# Protoboard_MX4-7-9.net
KiCad netlist of a schematic drawn in EAGLE
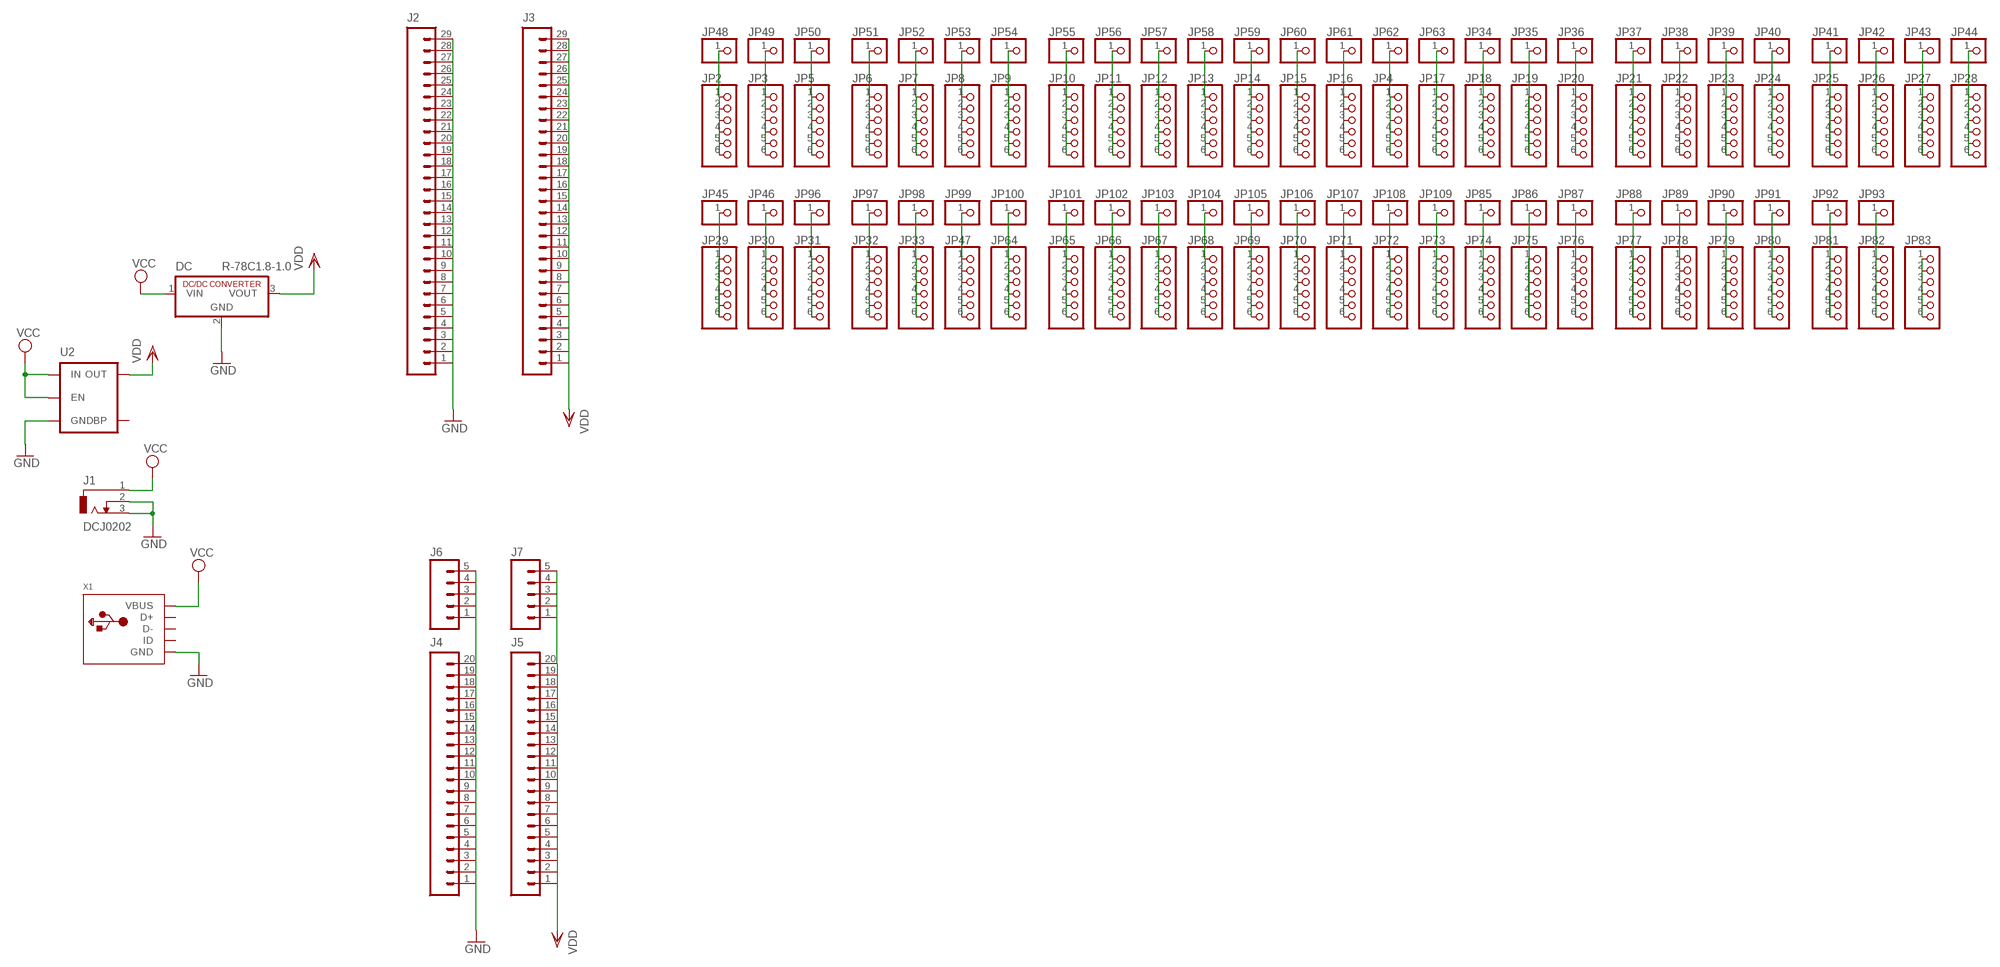
[diagram p0: schematic, sheet 1]

(export (version "E")
  (design (tool "Eeschema 10.0.6"))
  (components
    (comp (ref "DC")
      (value "R-78C1.8-1.0")
      (footprint "eagle-import:SIP3")
      (libsource (lib "eagle-import") (part "R-78C-1.01.8"))
    )
    (comp (ref "J1")
      (value "DCJ0202")
      (footprint "eagle-import:DCJ0202")
      (libsource (lib "eagle-import") (part "DCJ0202"))
    )
    (comp (ref "J2")
      (value "M29NO_SILK")
      (footprint "eagle-import:1X29_NO_SILK")
      (libsource (lib "eagle-import") (part "M29NO_SILK"))
    )
    (comp (ref "J3")
      (value "M29NO_SILK")
      (footprint "eagle-import:1X29_NO_SILK")
      (libsource (lib "eagle-import") (part "M29NO_SILK"))
    )
    (comp (ref "J4")
      (value "M20NO_SILK_KIT")
      (footprint "eagle-import:1X20_NO_SILK_KIT")
      (libsource (lib "eagle-import") (part "M20NO_SILK_KIT"))
    )
    (comp (ref "J5")
      (value "M20NO_SILK_KIT")
      (footprint "eagle-import:1X20_NO_SILK_KIT")
      (libsource (lib "eagle-import") (part "M20NO_SILK_KIT"))
    )
    (comp (ref "J6")
      (value "M05NO_SILK")
      (footprint "eagle-import:1X05_NO_SILK")
      (libsource (lib "eagle-import") (part "M05NO_SILK"))
    )
    (comp (ref "J7")
      (value "M05NO_SILK")
      (footprint "eagle-import:1X05_NO_SILK")
      (libsource (lib "eagle-import") (part "M05NO_SILK"))
    )
    (comp (ref "JP2")
      (value "PINHD-1X6CB")
      (footprint "eagle-import:1X06-CLEANBIG")
      (libsource (lib "eagle-import") (part "PINHD-1X6CB"))
    )
    (comp (ref "JP3")
      (value "PINHD-1X6CB")
      (footprint "eagle-import:1X06-CLEANBIG")
      (libsource (lib "eagle-import") (part "PINHD-1X6CB"))
    )
    (comp (ref "JP4")
      (value "PINHD-1X6CB")
      (footprint "eagle-import:1X06-CLEANBIG")
      (libsource (lib "eagle-import") (part "PINHD-1X6CB"))
    )
    (comp (ref "JP5")
      (value "PINHD-1X6CB")
      (footprint "eagle-import:1X06-CLEANBIG")
      (libsource (lib "eagle-import") (part "PINHD-1X6CB"))
    )
    (comp (ref "JP6")
      (value "PINHD-1X6CB")
      (footprint "eagle-import:1X06-CLEANBIG")
      (libsource (lib "eagle-import") (part "PINHD-1X6CB"))
    )
    (comp (ref "JP7")
      (value "PINHD-1X6CB")
      (footprint "eagle-import:1X06-CLEANBIG")
      (libsource (lib "eagle-import") (part "PINHD-1X6CB"))
    )
    (comp (ref "JP8")
      (value "PINHD-1X6CB")
      (footprint "eagle-import:1X06-CLEANBIG")
      (libsource (lib "eagle-import") (part "PINHD-1X6CB"))
    )
    (comp (ref "JP9")
      (value "PINHD-1X6CB")
      (footprint "eagle-import:1X06-CLEANBIG")
      (libsource (lib "eagle-import") (part "PINHD-1X6CB"))
    )
    (comp (ref "JP10")
      (value "PINHD-1X6CB")
      (footprint "eagle-import:1X06-CLEANBIG")
      (libsource (lib "eagle-import") (part "PINHD-1X6CB"))
    )
    (comp (ref "JP11")
      (value "PINHD-1X6CB")
      (footprint "eagle-import:1X06-CLEANBIG")
      (libsource (lib "eagle-import") (part "PINHD-1X6CB"))
    )
    (comp (ref "JP12")
      (value "PINHD-1X6CB")
      (footprint "eagle-import:1X06-CLEANBIG")
      (libsource (lib "eagle-import") (part "PINHD-1X6CB"))
    )
    (comp (ref "JP13")
      (value "PINHD-1X6CB")
      (footprint "eagle-import:1X06-CLEANBIG")
      (libsource (lib "eagle-import") (part "PINHD-1X6CB"))
    )
    (comp (ref "JP14")
      (value "PINHD-1X6CB")
      (footprint "eagle-import:1X06-CLEANBIG")
      (libsource (lib "eagle-import") (part "PINHD-1X6CB"))
    )
    (comp (ref "JP15")
      (value "PINHD-1X6CB")
      (footprint "eagle-import:1X06-CLEANBIG")
      (libsource (lib "eagle-import") (part "PINHD-1X6CB"))
    )
    (comp (ref "JP16")
      (value "PINHD-1X6CB")
      (footprint "eagle-import:1X06-CLEANBIG")
      (libsource (lib "eagle-import") (part "PINHD-1X6CB"))
    )
    (comp (ref "JP17")
      (value "PINHD-1X6CB")
      (footprint "eagle-import:1X06-CLEANBIG")
      (libsource (lib "eagle-import") (part "PINHD-1X6CB"))
    )
    (comp (ref "JP18")
      (value "PINHD-1X6CB")
      (footprint "eagle-import:1X06-CLEANBIG")
      (libsource (lib "eagle-import") (part "PINHD-1X6CB"))
    )
    (comp (ref "JP19")
      (value "PINHD-1X6CB")
      (footprint "eagle-import:1X06-CLEANBIG")
      (libsource (lib "eagle-import") (part "PINHD-1X6CB"))
    )
    (comp (ref "JP20")
      (value "PINHD-1X6CB")
      (footprint "eagle-import:1X06-CLEANBIG")
      (libsource (lib "eagle-import") (part "PINHD-1X6CB"))
    )
    (comp (ref "JP21")
      (value "PINHD-1X6CB")
      (footprint "eagle-import:1X06-CLEANBIG")
      (libsource (lib "eagle-import") (part "PINHD-1X6CB"))
    )
    (comp (ref "JP22")
      (value "PINHD-1X6CB")
      (footprint "eagle-import:1X06-CLEANBIG")
      (libsource (lib "eagle-import") (part "PINHD-1X6CB"))
    )
    (comp (ref "JP23")
      (value "PINHD-1X6CB")
      (footprint "eagle-import:1X06-CLEANBIG")
      (libsource (lib "eagle-import") (part "PINHD-1X6CB"))
    )
    (comp (ref "JP24")
      (value "PINHD-1X6CB")
      (footprint "eagle-import:1X06-CLEANBIG")
      (libsource (lib "eagle-import") (part "PINHD-1X6CB"))
    )
    (comp (ref "JP25")
      (value "PINHD-1X6CB")
      (footprint "eagle-import:1X06-CLEANBIG")
      (libsource (lib "eagle-import") (part "PINHD-1X6CB"))
    )
    (comp (ref "JP26")
      (value "PINHD-1X6CB")
      (footprint "eagle-import:1X06-CLEANBIG")
      (libsource (lib "eagle-import") (part "PINHD-1X6CB"))
    )
    (comp (ref "JP27")
      (value "PINHD-1X6CB")
      (footprint "eagle-import:1X06-CLEANBIG")
      (libsource (lib "eagle-import") (part "PINHD-1X6CB"))
    )
    (comp (ref "JP28")
      (value "PINHD-1X6CB")
      (footprint "eagle-import:1X06-CLEANBIG")
      (libsource (lib "eagle-import") (part "PINHD-1X6CB"))
    )
    (comp (ref "JP29")
      (value "PINHD-1X6CB")
      (footprint "eagle-import:1X06-CLEANBIG")
      (libsource (lib "eagle-import") (part "PINHD-1X6CB"))
    )
    (comp (ref "JP30")
      (value "PINHD-1X6CB")
      (footprint "eagle-import:1X06-CLEANBIG")
      (libsource (lib "eagle-import") (part "PINHD-1X6CB"))
    )
    (comp (ref "JP31")
      (value "PINHD-1X6CB")
      (footprint "eagle-import:1X06-CLEANBIG")
      (libsource (lib "eagle-import") (part "PINHD-1X6CB"))
    )
    (comp (ref "JP32")
      (value "PINHD-1X6CB")
      (footprint "eagle-import:1X06-CLEANBIG")
      (libsource (lib "eagle-import") (part "PINHD-1X6CB"))
    )
    (comp (ref "JP33")
      (value "PINHD-1X6CB")
      (footprint "eagle-import:1X06-CLEANBIG")
      (libsource (lib "eagle-import") (part "PINHD-1X6CB"))
    )
    (comp (ref "JP34")
      (value "PINHD-1X1CB")
      (footprint "eagle-import:1X01-CLEANBIG")
      (libsource (lib "eagle-import") (part "PINHD-1X1CB"))
    )
    (comp (ref "JP35")
      (value "PINHD-1X1CB")
      (footprint "eagle-import:1X01-CLEANBIG")
      (libsource (lib "eagle-import") (part "PINHD-1X1CB"))
    )
    (comp (ref "JP36")
      (value "PINHD-1X1CB")
      (footprint "eagle-import:1X01-CLEANBIG")
      (libsource (lib "eagle-import") (part "PINHD-1X1CB"))
    )
    (comp (ref "JP37")
      (value "PINHD-1X1CB")
      (footprint "eagle-import:1X01-CLEANBIG")
      (libsource (lib "eagle-import") (part "PINHD-1X1CB"))
    )
    (comp (ref "JP38")
      (value "PINHD-1X1CB")
      (footprint "eagle-import:1X01-CLEANBIG")
      (libsource (lib "eagle-import") (part "PINHD-1X1CB"))
    )
    (comp (ref "JP39")
      (value "PINHD-1X1CB")
      (footprint "eagle-import:1X01-CLEANBIG")
      (libsource (lib "eagle-import") (part "PINHD-1X1CB"))
    )
    (comp (ref "JP40")
      (value "PINHD-1X1CB")
      (footprint "eagle-import:1X01-CLEANBIG")
      (libsource (lib "eagle-import") (part "PINHD-1X1CB"))
    )
    (comp (ref "JP41")
      (value "PINHD-1X1CB")
      (footprint "eagle-import:1X01-CLEANBIG")
      (libsource (lib "eagle-import") (part "PINHD-1X1CB"))
    )
    (comp (ref "JP42")
      (value "PINHD-1X1CB")
      (footprint "eagle-import:1X01-CLEANBIG")
      (libsource (lib "eagle-import") (part "PINHD-1X1CB"))
    )
    (comp (ref "JP43")
      (value "PINHD-1X1CB")
      (footprint "eagle-import:1X01-CLEANBIG")
      (libsource (lib "eagle-import") (part "PINHD-1X1CB"))
    )
    (comp (ref "JP44")
      (value "PINHD-1X1CB")
      (footprint "eagle-import:1X01-CLEANBIG")
      (libsource (lib "eagle-import") (part "PINHD-1X1CB"))
    )
    (comp (ref "JP45")
      (value "PINHD-1X1CB")
      (footprint "eagle-import:1X01-CLEANBIG")
      (libsource (lib "eagle-import") (part "PINHD-1X1CB"))
    )
    (comp (ref "JP46")
      (value "PINHD-1X1CB")
      (footprint "eagle-import:1X01-CLEANBIG")
      (libsource (lib "eagle-import") (part "PINHD-1X1CB"))
    )
    (comp (ref "JP47")
      (value "PINHD-1X6CB")
      (footprint "eagle-import:1X06-CLEANBIG")
      (libsource (lib "eagle-import") (part "PINHD-1X6CB"))
    )
    (comp (ref "JP48")
      (value "PINHD-1X1CB")
      (footprint "eagle-import:1X01-CLEANBIG")
      (libsource (lib "eagle-import") (part "PINHD-1X1CB"))
    )
    (comp (ref "JP49")
      (value "PINHD-1X1CB")
      (footprint "eagle-import:1X01-CLEANBIG")
      (libsource (lib "eagle-import") (part "PINHD-1X1CB"))
    )
    (comp (ref "JP50")
      (value "PINHD-1X1CB")
      (footprint "eagle-import:1X01-CLEANBIG")
      (libsource (lib "eagle-import") (part "PINHD-1X1CB"))
    )
    (comp (ref "JP51")
      (value "PINHD-1X1CB")
      (footprint "eagle-import:1X01-CLEANBIG")
      (libsource (lib "eagle-import") (part "PINHD-1X1CB"))
    )
    (comp (ref "JP52")
      (value "PINHD-1X1CB")
      (footprint "eagle-import:1X01-CLEANBIG")
      (libsource (lib "eagle-import") (part "PINHD-1X1CB"))
    )
    (comp (ref "JP53")
      (value "PINHD-1X1CB")
      (footprint "eagle-import:1X01-CLEANBIG")
      (libsource (lib "eagle-import") (part "PINHD-1X1CB"))
    )
    (comp (ref "JP54")
      (value "PINHD-1X1CB")
      (footprint "eagle-import:1X01-CLEANBIG")
      (libsource (lib "eagle-import") (part "PINHD-1X1CB"))
    )
    (comp (ref "JP55")
      (value "PINHD-1X1CB")
      (footprint "eagle-import:1X01-CLEANBIG")
      (libsource (lib "eagle-import") (part "PINHD-1X1CB"))
    )
    (comp (ref "JP56")
      (value "PINHD-1X1CB")
      (footprint "eagle-import:1X01-CLEANBIG")
      (libsource (lib "eagle-import") (part "PINHD-1X1CB"))
    )
    (comp (ref "JP57")
      (value "PINHD-1X1CB")
      (footprint "eagle-import:1X01-CLEANBIG")
      (libsource (lib "eagle-import") (part "PINHD-1X1CB"))
    )
    (comp (ref "JP58")
      (value "PINHD-1X1CB")
      (footprint "eagle-import:1X01-CLEANBIG")
      (libsource (lib "eagle-import") (part "PINHD-1X1CB"))
    )
    (comp (ref "JP59")
      (value "PINHD-1X1CB")
      (footprint "eagle-import:1X01-CLEANBIG")
      (libsource (lib "eagle-import") (part "PINHD-1X1CB"))
    )
    (comp (ref "JP60")
      (value "PINHD-1X1CB")
      (footprint "eagle-import:1X01-CLEANBIG")
      (libsource (lib "eagle-import") (part "PINHD-1X1CB"))
    )
    (comp (ref "JP61")
      (value "PINHD-1X1CB")
      (footprint "eagle-import:1X01-CLEANBIG")
      (libsource (lib "eagle-import") (part "PINHD-1X1CB"))
    )
    (comp (ref "JP62")
      (value "PINHD-1X1CB")
      (footprint "eagle-import:1X01-CLEANBIG")
      (libsource (lib "eagle-import") (part "PINHD-1X1CB"))
    )
    (comp (ref "JP63")
      (value "PINHD-1X1CB")
      (footprint "eagle-import:1X01-CLEANBIG")
      (libsource (lib "eagle-import") (part "PINHD-1X1CB"))
    )
    (comp (ref "JP64")
      (value "PINHD-1X6CB")
      (footprint "eagle-import:1X06-CLEANBIG")
      (libsource (lib "eagle-import") (part "PINHD-1X6CB"))
    )
    (comp (ref "JP65")
      (value "PINHD-1X6CB")
      (footprint "eagle-import:1X06-CLEANBIG")
      (libsource (lib "eagle-import") (part "PINHD-1X6CB"))
    )
    (comp (ref "JP66")
      (value "PINHD-1X6CB")
      (footprint "eagle-import:1X06-CLEANBIG")
      (libsource (lib "eagle-import") (part "PINHD-1X6CB"))
    )
    (comp (ref "JP67")
      (value "PINHD-1X6CB")
      (footprint "eagle-import:1X06-CLEANBIG")
      (libsource (lib "eagle-import") (part "PINHD-1X6CB"))
    )
    (comp (ref "JP68")
      (value "PINHD-1X6CB")
      (footprint "eagle-import:1X06-CLEANBIG")
      (libsource (lib "eagle-import") (part "PINHD-1X6CB"))
    )
    (comp (ref "JP69")
      (value "PINHD-1X6CB")
      (footprint "eagle-import:1X06-CLEANBIG")
      (libsource (lib "eagle-import") (part "PINHD-1X6CB"))
    )
    (comp (ref "JP70")
      (value "PINHD-1X6CB")
      (footprint "eagle-import:1X06-CLEANBIG")
      (libsource (lib "eagle-import") (part "PINHD-1X6CB"))
    )
    (comp (ref "JP71")
      (value "PINHD-1X6CB")
      (footprint "eagle-import:1X06-CLEANBIG")
      (libsource (lib "eagle-import") (part "PINHD-1X6CB"))
    )
    (comp (ref "JP72")
      (value "PINHD-1X6CB")
      (footprint "eagle-import:1X06-CLEANBIG")
      (libsource (lib "eagle-import") (part "PINHD-1X6CB"))
    )
    (comp (ref "JP73")
      (value "PINHD-1X6CB")
      (footprint "eagle-import:1X06-CLEANBIG")
      (libsource (lib "eagle-import") (part "PINHD-1X6CB"))
    )
    (comp (ref "JP74")
      (value "PINHD-1X6CB")
      (footprint "eagle-import:1X06-CLEANBIG")
      (libsource (lib "eagle-import") (part "PINHD-1X6CB"))
    )
    (comp (ref "JP75")
      (value "PINHD-1X6CB")
      (footprint "eagle-import:1X06-CLEANBIG")
      (libsource (lib "eagle-import") (part "PINHD-1X6CB"))
    )
    (comp (ref "JP76")
      (value "PINHD-1X6CB")
      (footprint "eagle-import:1X06-CLEANBIG")
      (libsource (lib "eagle-import") (part "PINHD-1X6CB"))
    )
    (comp (ref "JP77")
      (value "PINHD-1X6CB")
      (footprint "eagle-import:1X06-CLEANBIG")
      (libsource (lib "eagle-import") (part "PINHD-1X6CB"))
    )
    (comp (ref "JP78")
      (value "PINHD-1X6CB")
      (footprint "eagle-import:1X06-CLEANBIG")
      (libsource (lib "eagle-import") (part "PINHD-1X6CB"))
    )
    (comp (ref "JP79")
      (value "PINHD-1X6CB")
      (footprint "eagle-import:1X06-CLEANBIG")
      (libsource (lib "eagle-import") (part "PINHD-1X6CB"))
    )
    (comp (ref "JP80")
      (value "PINHD-1X6CB")
      (footprint "eagle-import:1X06-CLEANBIG")
      (libsource (lib "eagle-import") (part "PINHD-1X6CB"))
    )
    (comp (ref "JP81")
      (value "PINHD-1X6CB")
      (footprint "eagle-import:1X06-CLEANBIG")
      (libsource (lib "eagle-import") (part "PINHD-1X6CB"))
    )
    (comp (ref "JP82")
      (value "PINHD-1X6CB")
      (footprint "eagle-import:1X06-CLEANBIG")
      (libsource (lib "eagle-import") (part "PINHD-1X6CB"))
    )
    (comp (ref "JP83")
      (value "PINHD-1X6CB")
      (footprint "eagle-import:1X06-CLEANBIG")
      (libsource (lib "eagle-import") (part "PINHD-1X6CB"))
    )
    (comp (ref "JP85")
      (value "PINHD-1X1CB")
      (footprint "eagle-import:1X01-CLEANBIG")
      (libsource (lib "eagle-import") (part "PINHD-1X1CB"))
    )
    (comp (ref "JP86")
      (value "PINHD-1X1CB")
      (footprint "eagle-import:1X01-CLEANBIG")
      (libsource (lib "eagle-import") (part "PINHD-1X1CB"))
    )
    (comp (ref "JP87")
      (value "PINHD-1X1CB")
      (footprint "eagle-import:1X01-CLEANBIG")
      (libsource (lib "eagle-import") (part "PINHD-1X1CB"))
    )
    (comp (ref "JP88")
      (value "PINHD-1X1CB")
      (footprint "eagle-import:1X01-CLEANBIG")
      (libsource (lib "eagle-import") (part "PINHD-1X1CB"))
    )
    (comp (ref "JP89")
      (value "PINHD-1X1CB")
      (footprint "eagle-import:1X01-CLEANBIG")
      (libsource (lib "eagle-import") (part "PINHD-1X1CB"))
    )
    (comp (ref "JP90")
      (value "PINHD-1X1CB")
      (footprint "eagle-import:1X01-CLEANBIG")
      (libsource (lib "eagle-import") (part "PINHD-1X1CB"))
    )
    (comp (ref "JP91")
      (value "PINHD-1X1CB")
      (footprint "eagle-import:1X01-CLEANBIG")
      (libsource (lib "eagle-import") (part "PINHD-1X1CB"))
    )
    (comp (ref "JP92")
      (value "PINHD-1X1CB")
      (footprint "eagle-import:1X01-CLEANBIG")
      (libsource (lib "eagle-import") (part "PINHD-1X1CB"))
    )
    (comp (ref "JP93")
      (value "PINHD-1X1CB")
      (footprint "eagle-import:1X01-CLEANBIG")
      (libsource (lib "eagle-import") (part "PINHD-1X1CB"))
    )
    (comp (ref "JP96")
      (value "PINHD-1X1CB")
      (footprint "eagle-import:1X01-CLEANBIG")
      (libsource (lib "eagle-import") (part "PINHD-1X1CB"))
    )
    (comp (ref "JP97")
      (value "PINHD-1X1CB")
      (footprint "eagle-import:1X01-CLEANBIG")
      (libsource (lib "eagle-import") (part "PINHD-1X1CB"))
    )
    (comp (ref "JP98")
      (value "PINHD-1X1CB")
      (footprint "eagle-import:1X01-CLEANBIG")
      (libsource (lib "eagle-import") (part "PINHD-1X1CB"))
    )
    (comp (ref "JP99")
      (value "PINHD-1X1CB")
      (footprint "eagle-import:1X01-CLEANBIG")
      (libsource (lib "eagle-import") (part "PINHD-1X1CB"))
    )
    (comp (ref "JP100")
      (value "PINHD-1X1CB")
      (footprint "eagle-import:1X01-CLEANBIG")
      (libsource (lib "eagle-import") (part "PINHD-1X1CB"))
    )
    (comp (ref "JP101")
      (value "PINHD-1X1CB")
      (footprint "eagle-import:1X01-CLEANBIG")
      (libsource (lib "eagle-import") (part "PINHD-1X1CB"))
    )
    (comp (ref "JP102")
      (value "PINHD-1X1CB")
      (footprint "eagle-import:1X01-CLEANBIG")
      (libsource (lib "eagle-import") (part "PINHD-1X1CB"))
    )
    (comp (ref "JP103")
      (value "PINHD-1X1CB")
      (footprint "eagle-import:1X01-CLEANBIG")
      (libsource (lib "eagle-import") (part "PINHD-1X1CB"))
    )
    (comp (ref "JP104")
      (value "PINHD-1X1CB")
      (footprint "eagle-import:1X01-CLEANBIG")
      (libsource (lib "eagle-import") (part "PINHD-1X1CB"))
    )
    (comp (ref "JP105")
      (value "PINHD-1X1CB")
      (footprint "eagle-import:1X01-CLEANBIG")
      (libsource (lib "eagle-import") (part "PINHD-1X1CB"))
    )
    (comp (ref "JP106")
      (value "PINHD-1X1CB")
      (footprint "eagle-import:1X01-CLEANBIG")
      (libsource (lib "eagle-import") (part "PINHD-1X1CB"))
    )
    (comp (ref "JP107")
      (value "PINHD-1X1CB")
      (footprint "eagle-import:1X01-CLEANBIG")
      (libsource (lib "eagle-import") (part "PINHD-1X1CB"))
    )
    (comp (ref "JP108")
      (value "PINHD-1X1CB")
      (footprint "eagle-import:1X01-CLEANBIG")
      (libsource (lib "eagle-import") (part "PINHD-1X1CB"))
    )
    (comp (ref "JP109")
      (value "PINHD-1X1CB")
      (footprint "eagle-import:1X01-CLEANBIG")
      (libsource (lib "eagle-import") (part "PINHD-1X1CB"))
    )
    (comp (ref "U2")
      (value "MIC52053.3V")
      (footprint "eagle-import:SOT23-5")
      (libsource (lib "eagle-import") (part "MIC52053.3V"))
    )
    (comp (ref "X1")
      (value "USBMICRO_20329")
      (footprint "eagle-import:4UCONN_20329")
      (libsource (lib "eagle-import") (part "USBMICRO_20329"))
    )
  )
  (nets
    (net (code "1") (name "GND") (class "Default")
      (node (ref "DC") (pin "2") (pinfunction "GND_2") (pintype "passive"))
      (node (ref "J1") (pin "2") (pinfunction "2_2") (pintype "passive"))
      (node (ref "J1") (pin "3") (pinfunction "3_3") (pintype "passive"))
      (node (ref "J2") (pin "1") (pinfunction "1_1") (pintype "passive"))
      (node (ref "J2") (pin "10") (pinfunction "10_10") (pintype "passive"))
      (node (ref "J2") (pin "11") (pinfunction "11_11") (pintype "passive"))
      (node (ref "J2") (pin "12") (pinfunction "12_12") (pintype "passive"))
      (node (ref "J2") (pin "13") (pinfunction "13_13") (pintype "passive"))
      (node (ref "J2") (pin "14") (pinfunction "14_14") (pintype "passive"))
      (node (ref "J2") (pin "15") (pinfunction "15_15") (pintype "passive"))
      (node (ref "J2") (pin "16") (pinfunction "16_16") (pintype "passive"))
      (node (ref "J2") (pin "17") (pinfunction "17_17") (pintype "passive"))
      (node (ref "J2") (pin "18") (pinfunction "18_18") (pintype "passive"))
      (node (ref "J2") (pin "19") (pinfunction "19_19") (pintype "passive"))
      (node (ref "J2") (pin "2") (pinfunction "2_2") (pintype "passive"))
      (node (ref "J2") (pin "20") (pinfunction "20_20") (pintype "passive"))
      (node (ref "J2") (pin "21") (pinfunction "21_21") (pintype "passive"))
      (node (ref "J2") (pin "22") (pinfunction "22_22") (pintype "passive"))
      (node (ref "J2") (pin "23") (pinfunction "23_23") (pintype "passive"))
      (node (ref "J2") (pin "24") (pinfunction "24_24") (pintype "passive"))
      (node (ref "J2") (pin "25") (pinfunction "25_25") (pintype "passive"))
      (node (ref "J2") (pin "26") (pinfunction "26_26") (pintype "passive"))
      (node (ref "J2") (pin "27") (pinfunction "27_27") (pintype "passive"))
      (node (ref "J2") (pin "28") (pinfunction "28_28") (pintype "passive"))
      (node (ref "J2") (pin "29") (pinfunction "29_29") (pintype "passive"))
      (node (ref "J2") (pin "3") (pinfunction "3_3") (pintype "passive"))
      (node (ref "J2") (pin "4") (pinfunction "4_4") (pintype "passive"))
      (node (ref "J2") (pin "5") (pinfunction "5_5") (pintype "passive"))
      (node (ref "J2") (pin "6") (pinfunction "6_6") (pintype "passive"))
      (node (ref "J2") (pin "7") (pinfunction "7_7") (pintype "passive"))
      (node (ref "J2") (pin "8") (pinfunction "8_8") (pintype "passive"))
      (node (ref "J2") (pin "9") (pinfunction "9_9") (pintype "passive"))
      (node (ref "J4") (pin "1") (pinfunction "1_1") (pintype "passive"))
      (node (ref "J4") (pin "10") (pinfunction "10_10") (pintype "passive"))
      (node (ref "J4") (pin "11") (pinfunction "11_11") (pintype "passive"))
      (node (ref "J4") (pin "12") (pinfunction "12_12") (pintype "passive"))
      (node (ref "J4") (pin "13") (pinfunction "13_13") (pintype "passive"))
      (node (ref "J4") (pin "14") (pinfunction "14_14") (pintype "passive"))
      (node (ref "J4") (pin "15") (pinfunction "15_15") (pintype "passive"))
      (node (ref "J4") (pin "16") (pinfunction "16_16") (pintype "passive"))
      (node (ref "J4") (pin "17") (pinfunction "17_17") (pintype "passive"))
      (node (ref "J4") (pin "18") (pinfunction "18_18") (pintype "passive"))
      (node (ref "J4") (pin "19") (pinfunction "19_19") (pintype "passive"))
      (node (ref "J4") (pin "2") (pinfunction "2_2") (pintype "passive"))
      (node (ref "J4") (pin "20") (pinfunction "20_20") (pintype "passive"))
      (node (ref "J4") (pin "3") (pinfunction "3_3") (pintype "passive"))
      (node (ref "J4") (pin "4") (pinfunction "4_4") (pintype "passive"))
      (node (ref "J4") (pin "5") (pinfunction "5_5") (pintype "passive"))
      (node (ref "J4") (pin "6") (pinfunction "6_6") (pintype "passive"))
      (node (ref "J4") (pin "7") (pinfunction "7_7") (pintype "passive"))
      (node (ref "J4") (pin "8") (pinfunction "8_8") (pintype "passive"))
      (node (ref "J4") (pin "9") (pinfunction "9_9") (pintype "passive"))
      (node (ref "J6") (pin "1") (pinfunction "1_1") (pintype "passive"))
      (node (ref "J6") (pin "2") (pinfunction "2_2") (pintype "passive"))
      (node (ref "J6") (pin "3") (pinfunction "3_3") (pintype "passive"))
      (node (ref "J6") (pin "4") (pinfunction "4_4") (pintype "passive"))
      (node (ref "J6") (pin "5") (pinfunction "5_5") (pintype "passive"))
      (node (ref "U2") (pin "2") (pinfunction "GND_2") (pintype "input"))
      (node (ref "X1") (pin "BASE@1") (pinfunction "GND_BASE@1") (pintype "power_in"))
      (node (ref "X1") (pin "BASE@2") (pinfunction "GND_BASE@2") (pintype "power_in"))
      (node (ref "X1") (pin "GND") (pinfunction "GND_GND") (pintype "power_in"))
      (node (ref "X1") (pin "SPRT@1") (pinfunction "GND_SPRT@1") (pintype "power_in"))
      (node (ref "X1") (pin "SPRT@2") (pinfunction "GND_SPRT@2") (pintype "power_in"))
      (node (ref "X1") (pin "SPRT@3") (pinfunction "GND_SPRT@3") (pintype "power_in"))
      (node (ref "X1") (pin "SPRT@4") (pinfunction "GND_SPRT@4") (pintype "power_in"))
    )
    (net (code "2") (name "Net-(JP2-Pad1)") (class "Default")
      (node (ref "JP2") (pin "1") (pinfunction "1_1") (pintype "passive"))
      (node (ref "JP2") (pin "2") (pinfunction "2_2") (pintype "passive"))
      (node (ref "JP2") (pin "3") (pinfunction "3_3") (pintype "passive"))
      (node (ref "JP2") (pin "4") (pinfunction "4_4") (pintype "passive"))
      (node (ref "JP2") (pin "5") (pinfunction "5_5") (pintype "passive"))
      (node (ref "JP2") (pin "6") (pinfunction "6_6") (pintype "passive"))
      (node (ref "JP48") (pin "1") (pinfunction "1_1") (pintype "passive"))
    )
    (net (code "3") (name "Net-(JP3-Pad1)") (class "Default")
      (node (ref "JP3") (pin "1") (pinfunction "1_1") (pintype "passive"))
      (node (ref "JP3") (pin "2") (pinfunction "2_2") (pintype "passive"))
      (node (ref "JP3") (pin "3") (pinfunction "3_3") (pintype "passive"))
      (node (ref "JP3") (pin "4") (pinfunction "4_4") (pintype "passive"))
      (node (ref "JP3") (pin "5") (pinfunction "5_5") (pintype "passive"))
      (node (ref "JP3") (pin "6") (pinfunction "6_6") (pintype "passive"))
      (node (ref "JP49") (pin "1") (pinfunction "1_1") (pintype "passive"))
    )
    (net (code "4") (name "Net-(JP4-Pad1)") (class "Default")
      (node (ref "JP4") (pin "1") (pinfunction "1_1") (pintype "passive"))
      (node (ref "JP4") (pin "2") (pinfunction "2_2") (pintype "passive"))
      (node (ref "JP4") (pin "3") (pinfunction "3_3") (pintype "passive"))
      (node (ref "JP4") (pin "4") (pinfunction "4_4") (pintype "passive"))
      (node (ref "JP4") (pin "5") (pinfunction "5_5") (pintype "passive"))
      (node (ref "JP4") (pin "6") (pinfunction "6_6") (pintype "passive"))
      (node (ref "JP62") (pin "1") (pinfunction "1_1") (pintype "passive"))
    )
    (net (code "5") (name "Net-(JP5-Pad1)") (class "Default")
      (node (ref "JP5") (pin "1") (pinfunction "1_1") (pintype "passive"))
      (node (ref "JP5") (pin "2") (pinfunction "2_2") (pintype "passive"))
      (node (ref "JP5") (pin "3") (pinfunction "3_3") (pintype "passive"))
      (node (ref "JP5") (pin "4") (pinfunction "4_4") (pintype "passive"))
      (node (ref "JP5") (pin "5") (pinfunction "5_5") (pintype "passive"))
      (node (ref "JP5") (pin "6") (pinfunction "6_6") (pintype "passive"))
      (node (ref "JP50") (pin "1") (pinfunction "1_1") (pintype "passive"))
    )
    (net (code "6") (name "Net-(JP10-Pad1)") (class "Default")
      (node (ref "JP10") (pin "1") (pinfunction "1_1") (pintype "passive"))
      (node (ref "JP10") (pin "2") (pinfunction "2_2") (pintype "passive"))
      (node (ref "JP10") (pin "3") (pinfunction "3_3") (pintype "passive"))
      (node (ref "JP10") (pin "4") (pinfunction "4_4") (pintype "passive"))
      (node (ref "JP10") (pin "5") (pinfunction "5_5") (pintype "passive"))
      (node (ref "JP10") (pin "6") (pinfunction "6_6") (pintype "passive"))
      (node (ref "JP55") (pin "1") (pinfunction "1_1") (pintype "passive"))
    )
    (net (code "7") (name "Net-(JP11-Pad1)") (class "Default")
      (node (ref "JP11") (pin "1") (pinfunction "1_1") (pintype "passive"))
      (node (ref "JP11") (pin "2") (pinfunction "2_2") (pintype "passive"))
      (node (ref "JP11") (pin "3") (pinfunction "3_3") (pintype "passive"))
      (node (ref "JP11") (pin "4") (pinfunction "4_4") (pintype "passive"))
      (node (ref "JP11") (pin "5") (pinfunction "5_5") (pintype "passive"))
      (node (ref "JP11") (pin "6") (pinfunction "6_6") (pintype "passive"))
      (node (ref "JP56") (pin "1") (pinfunction "1_1") (pintype "passive"))
    )
    (net (code "8") (name "Net-(JP12-Pad1)") (class "Default")
      (node (ref "JP12") (pin "1") (pinfunction "1_1") (pintype "passive"))
      (node (ref "JP12") (pin "2") (pinfunction "2_2") (pintype "passive"))
      (node (ref "JP12") (pin "3") (pinfunction "3_3") (pintype "passive"))
      (node (ref "JP12") (pin "4") (pinfunction "4_4") (pintype "passive"))
      (node (ref "JP12") (pin "5") (pinfunction "5_5") (pintype "passive"))
      (node (ref "JP12") (pin "6") (pinfunction "6_6") (pintype "passive"))
      (node (ref "JP57") (pin "1") (pinfunction "1_1") (pintype "passive"))
    )
    (net (code "9") (name "Net-(JP13-Pad1)") (class "Default")
      (node (ref "JP13") (pin "1") (pinfunction "1_1") (pintype "passive"))
      (node (ref "JP13") (pin "2") (pinfunction "2_2") (pintype "passive"))
      (node (ref "JP13") (pin "3") (pinfunction "3_3") (pintype "passive"))
      (node (ref "JP13") (pin "4") (pinfunction "4_4") (pintype "passive"))
      (node (ref "JP13") (pin "5") (pinfunction "5_5") (pintype "passive"))
      (node (ref "JP13") (pin "6") (pinfunction "6_6") (pintype "passive"))
      (node (ref "JP58") (pin "1") (pinfunction "1_1") (pintype "passive"))
    )
    (net (code "10") (name "Net-(JP14-Pad1)") (class "Default")
      (node (ref "JP14") (pin "1") (pinfunction "1_1") (pintype "passive"))
      (node (ref "JP14") (pin "2") (pinfunction "2_2") (pintype "passive"))
      (node (ref "JP14") (pin "3") (pinfunction "3_3") (pintype "passive"))
      (node (ref "JP14") (pin "4") (pinfunction "4_4") (pintype "passive"))
      (node (ref "JP14") (pin "5") (pinfunction "5_5") (pintype "passive"))
      (node (ref "JP14") (pin "6") (pinfunction "6_6") (pintype "passive"))
      (node (ref "JP59") (pin "1") (pinfunction "1_1") (pintype "passive"))
    )
    (net (code "11") (name "Net-(JP15-Pad1)") (class "Default")
      (node (ref "JP15") (pin "1") (pinfunction "1_1") (pintype "passive"))
      (node (ref "JP15") (pin "2") (pinfunction "2_2") (pintype "passive"))
      (node (ref "JP15") (pin "3") (pinfunction "3_3") (pintype "passive"))
      (node (ref "JP15") (pin "4") (pinfunction "4_4") (pintype "passive"))
      (node (ref "JP15") (pin "5") (pinfunction "5_5") (pintype "passive"))
      (node (ref "JP15") (pin "6") (pinfunction "6_6") (pintype "passive"))
      (node (ref "JP60") (pin "1") (pinfunction "1_1") (pintype "passive"))
    )
    (net (code "12") (name "Net-(JP16-Pad1)") (class "Default")
      (node (ref "JP16") (pin "1") (pinfunction "1_1") (pintype "passive"))
      (node (ref "JP16") (pin "2") (pinfunction "2_2") (pintype "passive"))
      (node (ref "JP16") (pin "3") (pinfunction "3_3") (pintype "passive"))
      (node (ref "JP16") (pin "4") (pinfunction "4_4") (pintype "passive"))
      (node (ref "JP16") (pin "5") (pinfunction "5_5") (pintype "passive"))
      (node (ref "JP16") (pin "6") (pinfunction "6_6") (pintype "passive"))
      (node (ref "JP61") (pin "1") (pinfunction "1_1") (pintype "passive"))
    )
    (net (code "13") (name "Net-(JP17-Pad1)") (class "Default")
      (node (ref "JP17") (pin "1") (pinfunction "1_1") (pintype "passive"))
      (node (ref "JP17") (pin "2") (pinfunction "2_2") (pintype "passive"))
      (node (ref "JP17") (pin "3") (pinfunction "3_3") (pintype "passive"))
      (node (ref "JP17") (pin "4") (pinfunction "4_4") (pintype "passive"))
      (node (ref "JP17") (pin "5") (pinfunction "5_5") (pintype "passive"))
      (node (ref "JP17") (pin "6") (pinfunction "6_6") (pintype "passive"))
      (node (ref "JP63") (pin "1") (pinfunction "1_1") (pintype "passive"))
    )
    (net (code "14") (name "Net-(JP18-Pad1)") (class "Default")
      (node (ref "JP18") (pin "1") (pinfunction "1_1") (pintype "passive"))
      (node (ref "JP18") (pin "2") (pinfunction "2_2") (pintype "passive"))
      (node (ref "JP18") (pin "3") (pinfunction "3_3") (pintype "passive"))
      (node (ref "JP18") (pin "4") (pinfunction "4_4") (pintype "passive"))
      (node (ref "JP18") (pin "5") (pinfunction "5_5") (pintype "passive"))
      (node (ref "JP18") (pin "6") (pinfunction "6_6") (pintype "passive"))
      (node (ref "JP34") (pin "1") (pinfunction "1_1") (pintype "passive"))
    )
    (net (code "15") (name "Net-(JP19-Pad1)") (class "Default")
      (node (ref "JP19") (pin "1") (pinfunction "1_1") (pintype "passive"))
      (node (ref "JP19") (pin "2") (pinfunction "2_2") (pintype "passive"))
      (node (ref "JP19") (pin "3") (pinfunction "3_3") (pintype "passive"))
      (node (ref "JP19") (pin "4") (pinfunction "4_4") (pintype "passive"))
      (node (ref "JP19") (pin "5") (pinfunction "5_5") (pintype "passive"))
      (node (ref "JP19") (pin "6") (pinfunction "6_6") (pintype "passive"))
      (node (ref "JP35") (pin "1") (pinfunction "1_1") (pintype "passive"))
    )
    (net (code "16") (name "Net-(JP20-Pad1)") (class "Default")
      (node (ref "JP20") (pin "1") (pinfunction "1_1") (pintype "passive"))
      (node (ref "JP20") (pin "2") (pinfunction "2_2") (pintype "passive"))
      (node (ref "JP20") (pin "3") (pinfunction "3_3") (pintype "passive"))
      (node (ref "JP20") (pin "4") (pinfunction "4_4") (pintype "passive"))
      (node (ref "JP20") (pin "5") (pinfunction "5_5") (pintype "passive"))
      (node (ref "JP20") (pin "6") (pinfunction "6_6") (pintype "passive"))
      (node (ref "JP36") (pin "1") (pinfunction "1_1") (pintype "passive"))
    )
    (net (code "17") (name "Net-(JP21-Pad1)") (class "Default")
      (node (ref "JP21") (pin "1") (pinfunction "1_1") (pintype "passive"))
      (node (ref "JP21") (pin "2") (pinfunction "2_2") (pintype "passive"))
      (node (ref "JP21") (pin "3") (pinfunction "3_3") (pintype "passive"))
      (node (ref "JP21") (pin "4") (pinfunction "4_4") (pintype "passive"))
      (node (ref "JP21") (pin "5") (pinfunction "5_5") (pintype "passive"))
      (node (ref "JP21") (pin "6") (pinfunction "6_6") (pintype "passive"))
      (node (ref "JP37") (pin "1") (pinfunction "1_1") (pintype "passive"))
    )
    (net (code "18") (name "Net-(JP22-Pad1)") (class "Default")
      (node (ref "JP22") (pin "1") (pinfunction "1_1") (pintype "passive"))
      (node (ref "JP22") (pin "2") (pinfunction "2_2") (pintype "passive"))
      (node (ref "JP22") (pin "3") (pinfunction "3_3") (pintype "passive"))
      (node (ref "JP22") (pin "4") (pinfunction "4_4") (pintype "passive"))
      (node (ref "JP22") (pin "5") (pinfunction "5_5") (pintype "passive"))
      (node (ref "JP22") (pin "6") (pinfunction "6_6") (pintype "passive"))
      (node (ref "JP38") (pin "1") (pinfunction "1_1") (pintype "passive"))
    )
    (net (code "19") (name "Net-(JP23-Pad1)") (class "Default")
      (node (ref "JP23") (pin "1") (pinfunction "1_1") (pintype "passive"))
      (node (ref "JP23") (pin "2") (pinfunction "2_2") (pintype "passive"))
      (node (ref "JP23") (pin "3") (pinfunction "3_3") (pintype "passive"))
      (node (ref "JP23") (pin "4") (pinfunction "4_4") (pintype "passive"))
      (node (ref "JP23") (pin "5") (pinfunction "5_5") (pintype "passive"))
      (node (ref "JP23") (pin "6") (pinfunction "6_6") (pintype "passive"))
      (node (ref "JP39") (pin "1") (pinfunction "1_1") (pintype "passive"))
    )
    (net (code "20") (name "Net-(JP24-Pad1)") (class "Default")
      (node (ref "JP24") (pin "1") (pinfunction "1_1") (pintype "passive"))
      (node (ref "JP24") (pin "2") (pinfunction "2_2") (pintype "passive"))
      (node (ref "JP24") (pin "3") (pinfunction "3_3") (pintype "passive"))
      (node (ref "JP24") (pin "4") (pinfunction "4_4") (pintype "passive"))
      (node (ref "JP24") (pin "5") (pinfunction "5_5") (pintype "passive"))
      (node (ref "JP24") (pin "6") (pinfunction "6_6") (pintype "passive"))
      (node (ref "JP40") (pin "1") (pinfunction "1_1") (pintype "passive"))
    )
    (net (code "21") (name "Net-(JP25-Pad1)") (class "Default")
      (node (ref "JP25") (pin "1") (pinfunction "1_1") (pintype "passive"))
      (node (ref "JP25") (pin "2") (pinfunction "2_2") (pintype "passive"))
      (node (ref "JP25") (pin "3") (pinfunction "3_3") (pintype "passive"))
      (node (ref "JP25") (pin "4") (pinfunction "4_4") (pintype "passive"))
      (node (ref "JP25") (pin "5") (pinfunction "5_5") (pintype "passive"))
      (node (ref "JP25") (pin "6") (pinfunction "6_6") (pintype "passive"))
      (node (ref "JP41") (pin "1") (pinfunction "1_1") (pintype "passive"))
    )
    (net (code "22") (name "Net-(JP26-Pad1)") (class "Default")
      (node (ref "JP26") (pin "1") (pinfunction "1_1") (pintype "passive"))
      (node (ref "JP26") (pin "2") (pinfunction "2_2") (pintype "passive"))
      (node (ref "JP26") (pin "3") (pinfunction "3_3") (pintype "passive"))
      (node (ref "JP26") (pin "4") (pinfunction "4_4") (pintype "passive"))
      (node (ref "JP26") (pin "5") (pinfunction "5_5") (pintype "passive"))
      (node (ref "JP26") (pin "6") (pinfunction "6_6") (pintype "passive"))
      (node (ref "JP42") (pin "1") (pinfunction "1_1") (pintype "passive"))
    )
    (net (code "23") (name "Net-(JP27-Pad1)") (class "Default")
      (node (ref "JP27") (pin "1") (pinfunction "1_1") (pintype "passive"))
      (node (ref "JP27") (pin "2") (pinfunction "2_2") (pintype "passive"))
      (node (ref "JP27") (pin "3") (pinfunction "3_3") (pintype "passive"))
      (node (ref "JP27") (pin "4") (pinfunction "4_4") (pintype "passive"))
      (node (ref "JP27") (pin "5") (pinfunction "5_5") (pintype "passive"))
      (node (ref "JP27") (pin "6") (pinfunction "6_6") (pintype "passive"))
      (node (ref "JP43") (pin "1") (pinfunction "1_1") (pintype "passive"))
    )
    (net (code "24") (name "Net-(JP28-Pad1)") (class "Default")
      (node (ref "JP28") (pin "1") (pinfunction "1_1") (pintype "passive"))
      (node (ref "JP28") (pin "2") (pinfunction "2_2") (pintype "passive"))
      (node (ref "JP28") (pin "3") (pinfunction "3_3") (pintype "passive"))
      (node (ref "JP28") (pin "4") (pinfunction "4_4") (pintype "passive"))
      (node (ref "JP28") (pin "5") (pinfunction "5_5") (pintype "passive"))
      (node (ref "JP28") (pin "6") (pinfunction "6_6") (pintype "passive"))
      (node (ref "JP44") (pin "1") (pinfunction "1_1") (pintype "passive"))
    )
    (net (code "25") (name "Net-(JP29-Pad1)") (class "Default")
      (node (ref "JP29") (pin "1") (pinfunction "1_1") (pintype "passive"))
      (node (ref "JP29") (pin "2") (pinfunction "2_2") (pintype "passive"))
      (node (ref "JP29") (pin "3") (pinfunction "3_3") (pintype "passive"))
      (node (ref "JP29") (pin "4") (pinfunction "4_4") (pintype "passive"))
      (node (ref "JP29") (pin "5") (pinfunction "5_5") (pintype "passive"))
      (node (ref "JP29") (pin "6") (pinfunction "6_6") (pintype "passive"))
      (node (ref "JP45") (pin "1") (pinfunction "1_1") (pintype "passive"))
    )
    (net (code "26") (name "Net-(JP30-Pad1)") (class "Default")
      (node (ref "JP30") (pin "1") (pinfunction "1_1") (pintype "passive"))
      (node (ref "JP30") (pin "2") (pinfunction "2_2") (pintype "passive"))
      (node (ref "JP30") (pin "3") (pinfunction "3_3") (pintype "passive"))
      (node (ref "JP30") (pin "4") (pinfunction "4_4") (pintype "passive"))
      (node (ref "JP30") (pin "5") (pinfunction "5_5") (pintype "passive"))
      (node (ref "JP30") (pin "6") (pinfunction "6_6") (pintype "passive"))
      (node (ref "JP46") (pin "1") (pinfunction "1_1") (pintype "passive"))
    )
    (net (code "27") (name "Net-(JP31-Pad1)") (class "Default")
      (node (ref "JP31") (pin "1") (pinfunction "1_1") (pintype "passive"))
      (node (ref "JP31") (pin "2") (pinfunction "2_2") (pintype "passive"))
      (node (ref "JP31") (pin "3") (pinfunction "3_3") (pintype "passive"))
      (node (ref "JP31") (pin "4") (pinfunction "4_4") (pintype "passive"))
      (node (ref "JP31") (pin "5") (pinfunction "5_5") (pintype "passive"))
      (node (ref "JP31") (pin "6") (pinfunction "6_6") (pintype "passive"))
      (node (ref "JP96") (pin "1") (pinfunction "1_1") (pintype "passive"))
    )
    (net (code "28") (name "Net-(JP32-Pad1)") (class "Default")
      (node (ref "JP32") (pin "1") (pinfunction "1_1") (pintype "passive"))
      (node (ref "JP32") (pin "2") (pinfunction "2_2") (pintype "passive"))
      (node (ref "JP32") (pin "3") (pinfunction "3_3") (pintype "passive"))
      (node (ref "JP32") (pin "4") (pinfunction "4_4") (pintype "passive"))
      (node (ref "JP32") (pin "5") (pinfunction "5_5") (pintype "passive"))
      (node (ref "JP32") (pin "6") (pinfunction "6_6") (pintype "passive"))
      (node (ref "JP97") (pin "1") (pinfunction "1_1") (pintype "passive"))
    )
    (net (code "29") (name "Net-(JP33-Pad1)") (class "Default")
      (node (ref "JP33") (pin "1") (pinfunction "1_1") (pintype "passive"))
      (node (ref "JP33") (pin "2") (pinfunction "2_2") (pintype "passive"))
      (node (ref "JP33") (pin "3") (pinfunction "3_3") (pintype "passive"))
      (node (ref "JP33") (pin "4") (pinfunction "4_4") (pintype "passive"))
      (node (ref "JP33") (pin "5") (pinfunction "5_5") (pintype "passive"))
      (node (ref "JP33") (pin "6") (pinfunction "6_6") (pintype "passive"))
      (node (ref "JP98") (pin "1") (pinfunction "1_1") (pintype "passive"))
    )
    (net (code "30") (name "Net-(JP47-Pad1)") (class "Default")
      (node (ref "JP47") (pin "1") (pinfunction "1_1") (pintype "passive"))
      (node (ref "JP47") (pin "2") (pinfunction "2_2") (pintype "passive"))
      (node (ref "JP47") (pin "3") (pinfunction "3_3") (pintype "passive"))
      (node (ref "JP47") (pin "4") (pinfunction "4_4") (pintype "passive"))
      (node (ref "JP47") (pin "5") (pinfunction "5_5") (pintype "passive"))
      (node (ref "JP47") (pin "6") (pinfunction "6_6") (pintype "passive"))
      (node (ref "JP99") (pin "1") (pinfunction "1_1") (pintype "passive"))
    )
    (net (code "31") (name "Net-(JP51-Pad1)") (class "Default")
      (node (ref "JP51") (pin "1") (pinfunction "1_1") (pintype "passive"))
      (node (ref "JP6") (pin "1") (pinfunction "1_1") (pintype "passive"))
      (node (ref "JP6") (pin "2") (pinfunction "2_2") (pintype "passive"))
      (node (ref "JP6") (pin "3") (pinfunction "3_3") (pintype "passive"))
      (node (ref "JP6") (pin "4") (pinfunction "4_4") (pintype "passive"))
      (node (ref "JP6") (pin "5") (pinfunction "5_5") (pintype "passive"))
      (node (ref "JP6") (pin "6") (pinfunction "6_6") (pintype "passive"))
    )
    (net (code "32") (name "Net-(JP52-Pad1)") (class "Default")
      (node (ref "JP52") (pin "1") (pinfunction "1_1") (pintype "passive"))
      (node (ref "JP7") (pin "1") (pinfunction "1_1") (pintype "passive"))
      (node (ref "JP7") (pin "2") (pinfunction "2_2") (pintype "passive"))
      (node (ref "JP7") (pin "3") (pinfunction "3_3") (pintype "passive"))
      (node (ref "JP7") (pin "4") (pinfunction "4_4") (pintype "passive"))
      (node (ref "JP7") (pin "5") (pinfunction "5_5") (pintype "passive"))
      (node (ref "JP7") (pin "6") (pinfunction "6_6") (pintype "passive"))
    )
    (net (code "33") (name "Net-(JP53-Pad1)") (class "Default")
      (node (ref "JP53") (pin "1") (pinfunction "1_1") (pintype "passive"))
      (node (ref "JP8") (pin "1") (pinfunction "1_1") (pintype "passive"))
      (node (ref "JP8") (pin "2") (pinfunction "2_2") (pintype "passive"))
      (node (ref "JP8") (pin "3") (pinfunction "3_3") (pintype "passive"))
      (node (ref "JP8") (pin "4") (pinfunction "4_4") (pintype "passive"))
      (node (ref "JP8") (pin "5") (pinfunction "5_5") (pintype "passive"))
      (node (ref "JP8") (pin "6") (pinfunction "6_6") (pintype "passive"))
    )
    (net (code "34") (name "Net-(JP54-Pad1)") (class "Default")
      (node (ref "JP54") (pin "1") (pinfunction "1_1") (pintype "passive"))
      (node (ref "JP9") (pin "1") (pinfunction "1_1") (pintype "passive"))
      (node (ref "JP9") (pin "2") (pinfunction "2_2") (pintype "passive"))
      (node (ref "JP9") (pin "3") (pinfunction "3_3") (pintype "passive"))
      (node (ref "JP9") (pin "4") (pinfunction "4_4") (pintype "passive"))
      (node (ref "JP9") (pin "5") (pinfunction "5_5") (pintype "passive"))
      (node (ref "JP9") (pin "6") (pinfunction "6_6") (pintype "passive"))
    )
    (net (code "35") (name "Net-(JP74-Pad1)") (class "Default")
      (node (ref "JP74") (pin "1") (pinfunction "1_1") (pintype "passive"))
      (node (ref "JP74") (pin "2") (pinfunction "2_2") (pintype "passive"))
      (node (ref "JP74") (pin "3") (pinfunction "3_3") (pintype "passive"))
      (node (ref "JP74") (pin "4") (pinfunction "4_4") (pintype "passive"))
      (node (ref "JP74") (pin "5") (pinfunction "5_5") (pintype "passive"))
      (node (ref "JP74") (pin "6") (pinfunction "6_6") (pintype "passive"))
      (node (ref "JP85") (pin "1") (pinfunction "1_1") (pintype "passive"))
    )
    (net (code "36") (name "Net-(JP75-Pad1)") (class "Default")
      (node (ref "JP75") (pin "1") (pinfunction "1_1") (pintype "passive"))
      (node (ref "JP75") (pin "2") (pinfunction "2_2") (pintype "passive"))
      (node (ref "JP75") (pin "3") (pinfunction "3_3") (pintype "passive"))
      (node (ref "JP75") (pin "4") (pinfunction "4_4") (pintype "passive"))
      (node (ref "JP75") (pin "5") (pinfunction "5_5") (pintype "passive"))
      (node (ref "JP75") (pin "6") (pinfunction "6_6") (pintype "passive"))
      (node (ref "JP86") (pin "1") (pinfunction "1_1") (pintype "passive"))
    )
    (net (code "37") (name "Net-(JP76-Pad1)") (class "Default")
      (node (ref "JP76") (pin "1") (pinfunction "1_1") (pintype "passive"))
      (node (ref "JP76") (pin "2") (pinfunction "2_2") (pintype "passive"))
      (node (ref "JP76") (pin "3") (pinfunction "3_3") (pintype "passive"))
      (node (ref "JP76") (pin "4") (pinfunction "4_4") (pintype "passive"))
      (node (ref "JP76") (pin "5") (pinfunction "5_5") (pintype "passive"))
      (node (ref "JP76") (pin "6") (pinfunction "6_6") (pintype "passive"))
      (node (ref "JP87") (pin "1") (pinfunction "1_1") (pintype "passive"))
    )
    (net (code "38") (name "Net-(JP77-Pad1)") (class "Default")
      (node (ref "JP77") (pin "1") (pinfunction "1_1") (pintype "passive"))
      (node (ref "JP77") (pin "2") (pinfunction "2_2") (pintype "passive"))
      (node (ref "JP77") (pin "3") (pinfunction "3_3") (pintype "passive"))
      (node (ref "JP77") (pin "4") (pinfunction "4_4") (pintype "passive"))
      (node (ref "JP77") (pin "5") (pinfunction "5_5") (pintype "passive"))
      (node (ref "JP77") (pin "6") (pinfunction "6_6") (pintype "passive"))
      (node (ref "JP88") (pin "1") (pinfunction "1_1") (pintype "passive"))
    )
    (net (code "39") (name "Net-(JP78-Pad1)") (class "Default")
      (node (ref "JP78") (pin "1") (pinfunction "1_1") (pintype "passive"))
      (node (ref "JP78") (pin "2") (pinfunction "2_2") (pintype "passive"))
      (node (ref "JP78") (pin "3") (pinfunction "3_3") (pintype "passive"))
      (node (ref "JP78") (pin "4") (pinfunction "4_4") (pintype "passive"))
      (node (ref "JP78") (pin "5") (pinfunction "5_5") (pintype "passive"))
      (node (ref "JP78") (pin "6") (pinfunction "6_6") (pintype "passive"))
      (node (ref "JP89") (pin "1") (pinfunction "1_1") (pintype "passive"))
    )
    (net (code "40") (name "Net-(JP79-Pad1)") (class "Default")
      (node (ref "JP79") (pin "1") (pinfunction "1_1") (pintype "passive"))
      (node (ref "JP79") (pin "2") (pinfunction "2_2") (pintype "passive"))
      (node (ref "JP79") (pin "3") (pinfunction "3_3") (pintype "passive"))
      (node (ref "JP79") (pin "4") (pinfunction "4_4") (pintype "passive"))
      (node (ref "JP79") (pin "5") (pinfunction "5_5") (pintype "passive"))
      (node (ref "JP79") (pin "6") (pinfunction "6_6") (pintype "passive"))
      (node (ref "JP90") (pin "1") (pinfunction "1_1") (pintype "passive"))
    )
    (net (code "41") (name "Net-(JP80-Pad1)") (class "Default")
      (node (ref "JP80") (pin "1") (pinfunction "1_1") (pintype "passive"))
      (node (ref "JP80") (pin "2") (pinfunction "2_2") (pintype "passive"))
      (node (ref "JP80") (pin "3") (pinfunction "3_3") (pintype "passive"))
      (node (ref "JP80") (pin "4") (pinfunction "4_4") (pintype "passive"))
      (node (ref "JP80") (pin "5") (pinfunction "5_5") (pintype "passive"))
      (node (ref "JP80") (pin "6") (pinfunction "6_6") (pintype "passive"))
      (node (ref "JP91") (pin "1") (pinfunction "1_1") (pintype "passive"))
    )
    (net (code "42") (name "Net-(JP81-Pad1)") (class "Default")
      (node (ref "JP81") (pin "1") (pinfunction "1_1") (pintype "passive"))
      (node (ref "JP81") (pin "2") (pinfunction "2_2") (pintype "passive"))
      (node (ref "JP81") (pin "3") (pinfunction "3_3") (pintype "passive"))
      (node (ref "JP81") (pin "4") (pinfunction "4_4") (pintype "passive"))
      (node (ref "JP81") (pin "5") (pinfunction "5_5") (pintype "passive"))
      (node (ref "JP81") (pin "6") (pinfunction "6_6") (pintype "passive"))
      (node (ref "JP92") (pin "1") (pinfunction "1_1") (pintype "passive"))
    )
    (net (code "43") (name "Net-(JP82-Pad1)") (class "Default")
      (node (ref "JP82") (pin "1") (pinfunction "1_1") (pintype "passive"))
      (node (ref "JP82") (pin "2") (pinfunction "2_2") (pintype "passive"))
      (node (ref "JP82") (pin "3") (pinfunction "3_3") (pintype "passive"))
      (node (ref "JP82") (pin "4") (pinfunction "4_4") (pintype "passive"))
      (node (ref "JP82") (pin "5") (pinfunction "5_5") (pintype "passive"))
      (node (ref "JP82") (pin "6") (pinfunction "6_6") (pintype "passive"))
      (node (ref "JP93") (pin "1") (pinfunction "1_1") (pintype "passive"))
    )
    (net (code "44") (name "Net-(JP83-Pad1)") (class "Default")
      (node (ref "JP83") (pin "1") (pinfunction "1_1") (pintype "passive"))
      (node (ref "JP83") (pin "2") (pinfunction "2_2") (pintype "passive"))
      (node (ref "JP83") (pin "3") (pinfunction "3_3") (pintype "passive"))
      (node (ref "JP83") (pin "4") (pinfunction "4_4") (pintype "passive"))
      (node (ref "JP83") (pin "5") (pinfunction "5_5") (pintype "passive"))
      (node (ref "JP83") (pin "6") (pinfunction "6_6") (pintype "passive"))
    )
    (net (code "45") (name "Net-(JP100-Pad1)") (class "Default")
      (node (ref "JP100") (pin "1") (pinfunction "1_1") (pintype "passive"))
      (node (ref "JP64") (pin "1") (pinfunction "1_1") (pintype "passive"))
      (node (ref "JP64") (pin "2") (pinfunction "2_2") (pintype "passive"))
      (node (ref "JP64") (pin "3") (pinfunction "3_3") (pintype "passive"))
      (node (ref "JP64") (pin "4") (pinfunction "4_4") (pintype "passive"))
      (node (ref "JP64") (pin "5") (pinfunction "5_5") (pintype "passive"))
      (node (ref "JP64") (pin "6") (pinfunction "6_6") (pintype "passive"))
    )
    (net (code "46") (name "Net-(JP101-Pad1)") (class "Default")
      (node (ref "JP101") (pin "1") (pinfunction "1_1") (pintype "passive"))
      (node (ref "JP65") (pin "1") (pinfunction "1_1") (pintype "passive"))
      (node (ref "JP65") (pin "2") (pinfunction "2_2") (pintype "passive"))
      (node (ref "JP65") (pin "3") (pinfunction "3_3") (pintype "passive"))
      (node (ref "JP65") (pin "4") (pinfunction "4_4") (pintype "passive"))
      (node (ref "JP65") (pin "5") (pinfunction "5_5") (pintype "passive"))
      (node (ref "JP65") (pin "6") (pinfunction "6_6") (pintype "passive"))
    )
    (net (code "47") (name "Net-(JP102-Pad1)") (class "Default")
      (node (ref "JP102") (pin "1") (pinfunction "1_1") (pintype "passive"))
      (node (ref "JP66") (pin "1") (pinfunction "1_1") (pintype "passive"))
      (node (ref "JP66") (pin "2") (pinfunction "2_2") (pintype "passive"))
      (node (ref "JP66") (pin "3") (pinfunction "3_3") (pintype "passive"))
      (node (ref "JP66") (pin "4") (pinfunction "4_4") (pintype "passive"))
      (node (ref "JP66") (pin "5") (pinfunction "5_5") (pintype "passive"))
      (node (ref "JP66") (pin "6") (pinfunction "6_6") (pintype "passive"))
    )
    (net (code "48") (name "Net-(JP103-Pad1)") (class "Default")
      (node (ref "JP103") (pin "1") (pinfunction "1_1") (pintype "passive"))
      (node (ref "JP67") (pin "1") (pinfunction "1_1") (pintype "passive"))
      (node (ref "JP67") (pin "2") (pinfunction "2_2") (pintype "passive"))
      (node (ref "JP67") (pin "3") (pinfunction "3_3") (pintype "passive"))
      (node (ref "JP67") (pin "4") (pinfunction "4_4") (pintype "passive"))
      (node (ref "JP67") (pin "5") (pinfunction "5_5") (pintype "passive"))
      (node (ref "JP67") (pin "6") (pinfunction "6_6") (pintype "passive"))
    )
    (net (code "49") (name "Net-(JP104-Pad1)") (class "Default")
      (node (ref "JP104") (pin "1") (pinfunction "1_1") (pintype "passive"))
      (node (ref "JP68") (pin "1") (pinfunction "1_1") (pintype "passive"))
      (node (ref "JP68") (pin "2") (pinfunction "2_2") (pintype "passive"))
      (node (ref "JP68") (pin "3") (pinfunction "3_3") (pintype "passive"))
      (node (ref "JP68") (pin "4") (pinfunction "4_4") (pintype "passive"))
      (node (ref "JP68") (pin "5") (pinfunction "5_5") (pintype "passive"))
      (node (ref "JP68") (pin "6") (pinfunction "6_6") (pintype "passive"))
    )
    (net (code "50") (name "Net-(JP105-Pad1)") (class "Default")
      (node (ref "JP105") (pin "1") (pinfunction "1_1") (pintype "passive"))
      (node (ref "JP69") (pin "1") (pinfunction "1_1") (pintype "passive"))
      (node (ref "JP69") (pin "2") (pinfunction "2_2") (pintype "passive"))
      (node (ref "JP69") (pin "3") (pinfunction "3_3") (pintype "passive"))
      (node (ref "JP69") (pin "4") (pinfunction "4_4") (pintype "passive"))
      (node (ref "JP69") (pin "5") (pinfunction "5_5") (pintype "passive"))
      (node (ref "JP69") (pin "6") (pinfunction "6_6") (pintype "passive"))
    )
    (net (code "51") (name "Net-(JP106-Pad1)") (class "Default")
      (node (ref "JP106") (pin "1") (pinfunction "1_1") (pintype "passive"))
      (node (ref "JP70") (pin "1") (pinfunction "1_1") (pintype "passive"))
      (node (ref "JP70") (pin "2") (pinfunction "2_2") (pintype "passive"))
      (node (ref "JP70") (pin "3") (pinfunction "3_3") (pintype "passive"))
      (node (ref "JP70") (pin "4") (pinfunction "4_4") (pintype "passive"))
      (node (ref "JP70") (pin "5") (pinfunction "5_5") (pintype "passive"))
      (node (ref "JP70") (pin "6") (pinfunction "6_6") (pintype "passive"))
    )
    (net (code "52") (name "Net-(JP107-Pad1)") (class "Default")
      (node (ref "JP107") (pin "1") (pinfunction "1_1") (pintype "passive"))
      (node (ref "JP71") (pin "1") (pinfunction "1_1") (pintype "passive"))
      (node (ref "JP71") (pin "2") (pinfunction "2_2") (pintype "passive"))
      (node (ref "JP71") (pin "3") (pinfunction "3_3") (pintype "passive"))
      (node (ref "JP71") (pin "4") (pinfunction "4_4") (pintype "passive"))
      (node (ref "JP71") (pin "5") (pinfunction "5_5") (pintype "passive"))
      (node (ref "JP71") (pin "6") (pinfunction "6_6") (pintype "passive"))
    )
    (net (code "53") (name "Net-(JP108-Pad1)") (class "Default")
      (node (ref "JP108") (pin "1") (pinfunction "1_1") (pintype "passive"))
      (node (ref "JP72") (pin "1") (pinfunction "1_1") (pintype "passive"))
      (node (ref "JP72") (pin "2") (pinfunction "2_2") (pintype "passive"))
      (node (ref "JP72") (pin "3") (pinfunction "3_3") (pintype "passive"))
      (node (ref "JP72") (pin "4") (pinfunction "4_4") (pintype "passive"))
      (node (ref "JP72") (pin "5") (pinfunction "5_5") (pintype "passive"))
      (node (ref "JP72") (pin "6") (pinfunction "6_6") (pintype "passive"))
    )
    (net (code "54") (name "Net-(JP109-Pad1)") (class "Default")
      (node (ref "JP109") (pin "1") (pinfunction "1_1") (pintype "passive"))
      (node (ref "JP73") (pin "1") (pinfunction "1_1") (pintype "passive"))
      (node (ref "JP73") (pin "2") (pinfunction "2_2") (pintype "passive"))
      (node (ref "JP73") (pin "3") (pinfunction "3_3") (pintype "passive"))
      (node (ref "JP73") (pin "4") (pinfunction "4_4") (pintype "passive"))
      (node (ref "JP73") (pin "5") (pinfunction "5_5") (pintype "passive"))
      (node (ref "JP73") (pin "6") (pinfunction "6_6") (pintype "passive"))
    )
    (net (code "55") (name "VCC") (class "Default")
      (node (ref "DC") (pin "1") (pinfunction "VIN_1") (pintype "passive"))
      (node (ref "J1") (pin "1") (pinfunction "1_1") (pintype "passive"))
      (node (ref "U2") (pin "1") (pinfunction "IN_1") (pintype "input"))
      (node (ref "U2") (pin "3") (pinfunction "EN_3") (pintype "input"))
      (node (ref "X1") (pin "VBUS") (pinfunction "VBUS_VBUS") (pintype "power_in"))
    )
    (net (code "56") (name "VDD") (class "Default")
      (node (ref "DC") (pin "3") (pinfunction "VOUT_3") (pintype "passive"))
      (node (ref "J3") (pin "1") (pinfunction "1_1") (pintype "passive"))
      (node (ref "J3") (pin "10") (pinfunction "10_10") (pintype "passive"))
      (node (ref "J3") (pin "11") (pinfunction "11_11") (pintype "passive"))
      (node (ref "J3") (pin "12") (pinfunction "12_12") (pintype "passive"))
      (node (ref "J3") (pin "13") (pinfunction "13_13") (pintype "passive"))
      (node (ref "J3") (pin "14") (pinfunction "14_14") (pintype "passive"))
      (node (ref "J3") (pin "15") (pinfunction "15_15") (pintype "passive"))
      (node (ref "J3") (pin "16") (pinfunction "16_16") (pintype "passive"))
      (node (ref "J3") (pin "17") (pinfunction "17_17") (pintype "passive"))
      (node (ref "J3") (pin "18") (pinfunction "18_18") (pintype "passive"))
      (node (ref "J3") (pin "19") (pinfunction "19_19") (pintype "passive"))
      (node (ref "J3") (pin "2") (pinfunction "2_2") (pintype "passive"))
      (node (ref "J3") (pin "20") (pinfunction "20_20") (pintype "passive"))
      (node (ref "J3") (pin "21") (pinfunction "21_21") (pintype "passive"))
      (node (ref "J3") (pin "22") (pinfunction "22_22") (pintype "passive"))
      (node (ref "J3") (pin "23") (pinfunction "23_23") (pintype "passive"))
      (node (ref "J3") (pin "24") (pinfunction "24_24") (pintype "passive"))
      (node (ref "J3") (pin "25") (pinfunction "25_25") (pintype "passive"))
      (node (ref "J3") (pin "26") (pinfunction "26_26") (pintype "passive"))
      (node (ref "J3") (pin "27") (pinfunction "27_27") (pintype "passive"))
      (node (ref "J3") (pin "28") (pinfunction "28_28") (pintype "passive"))
      (node (ref "J3") (pin "29") (pinfunction "29_29") (pintype "passive"))
      (node (ref "J3") (pin "3") (pinfunction "3_3") (pintype "passive"))
      (node (ref "J3") (pin "4") (pinfunction "4_4") (pintype "passive"))
      (node (ref "J3") (pin "5") (pinfunction "5_5") (pintype "passive"))
      (node (ref "J3") (pin "6") (pinfunction "6_6") (pintype "passive"))
      (node (ref "J3") (pin "7") (pinfunction "7_7") (pintype "passive"))
      (node (ref "J3") (pin "8") (pinfunction "8_8") (pintype "passive"))
      (node (ref "J3") (pin "9") (pinfunction "9_9") (pintype "passive"))
      (node (ref "J5") (pin "1") (pinfunction "1_1") (pintype "passive"))
      (node (ref "J5") (pin "10") (pinfunction "10_10") (pintype "passive"))
      (node (ref "J5") (pin "11") (pinfunction "11_11") (pintype "passive"))
      (node (ref "J5") (pin "12") (pinfunction "12_12") (pintype "passive"))
      (node (ref "J5") (pin "13") (pinfunction "13_13") (pintype "passive"))
      (node (ref "J5") (pin "14") (pinfunction "14_14") (pintype "passive"))
      (node (ref "J5") (pin "15") (pinfunction "15_15") (pintype "passive"))
      (node (ref "J5") (pin "16") (pinfunction "16_16") (pintype "passive"))
      (node (ref "J5") (pin "17") (pinfunction "17_17") (pintype "passive"))
      (node (ref "J5") (pin "18") (pinfunction "18_18") (pintype "passive"))
      (node (ref "J5") (pin "19") (pinfunction "19_19") (pintype "passive"))
      (node (ref "J5") (pin "2") (pinfunction "2_2") (pintype "passive"))
      (node (ref "J5") (pin "20") (pinfunction "20_20") (pintype "passive"))
      (node (ref "J5") (pin "3") (pinfunction "3_3") (pintype "passive"))
      (node (ref "J5") (pin "4") (pinfunction "4_4") (pintype "passive"))
      (node (ref "J5") (pin "5") (pinfunction "5_5") (pintype "passive"))
      (node (ref "J5") (pin "6") (pinfunction "6_6") (pintype "passive"))
      (node (ref "J5") (pin "7") (pinfunction "7_7") (pintype "passive"))
      (node (ref "J5") (pin "8") (pinfunction "8_8") (pintype "passive"))
      (node (ref "J5") (pin "9") (pinfunction "9_9") (pintype "passive"))
      (node (ref "J7") (pin "1") (pinfunction "1_1") (pintype "passive"))
      (node (ref "J7") (pin "2") (pinfunction "2_2") (pintype "passive"))
      (node (ref "J7") (pin "3") (pinfunction "3_3") (pintype "passive"))
      (node (ref "J7") (pin "4") (pinfunction "4_4") (pintype "passive"))
      (node (ref "J7") (pin "5") (pinfunction "5_5") (pintype "passive"))
      (node (ref "U2") (pin "5") (pinfunction "OUT_5") (pintype "passive"))
    )
    (net (code "57") (name "unconnected-(U2-BP-Pad4)") (class "Default")
      (node (ref "U2") (pin "4") (pinfunction "BP_4") (pintype "input"))
    )
    (net (code "58") (name "unconnected-(X1-PadD+)") (class "Default")
      (node (ref "X1") (pin "D+") (pinfunction "D+_D+") (pintype "bidirectional"))
    )
    (net (code "59") (name "unconnected-(X1-PadD-)") (class "Default")
      (node (ref "X1") (pin "D-") (pinfunction "D-_D-") (pintype "bidirectional"))
    )
    (net (code "60") (name "unconnected-(X1-PadID)") (class "Default")
      (node (ref "X1") (pin "ID") (pinfunction "ID_ID") (pintype "bidirectional"))
    )
  )
)
